# PIR-ESP-V10.net
KiCad netlist of a schematic drawn in EAGLE
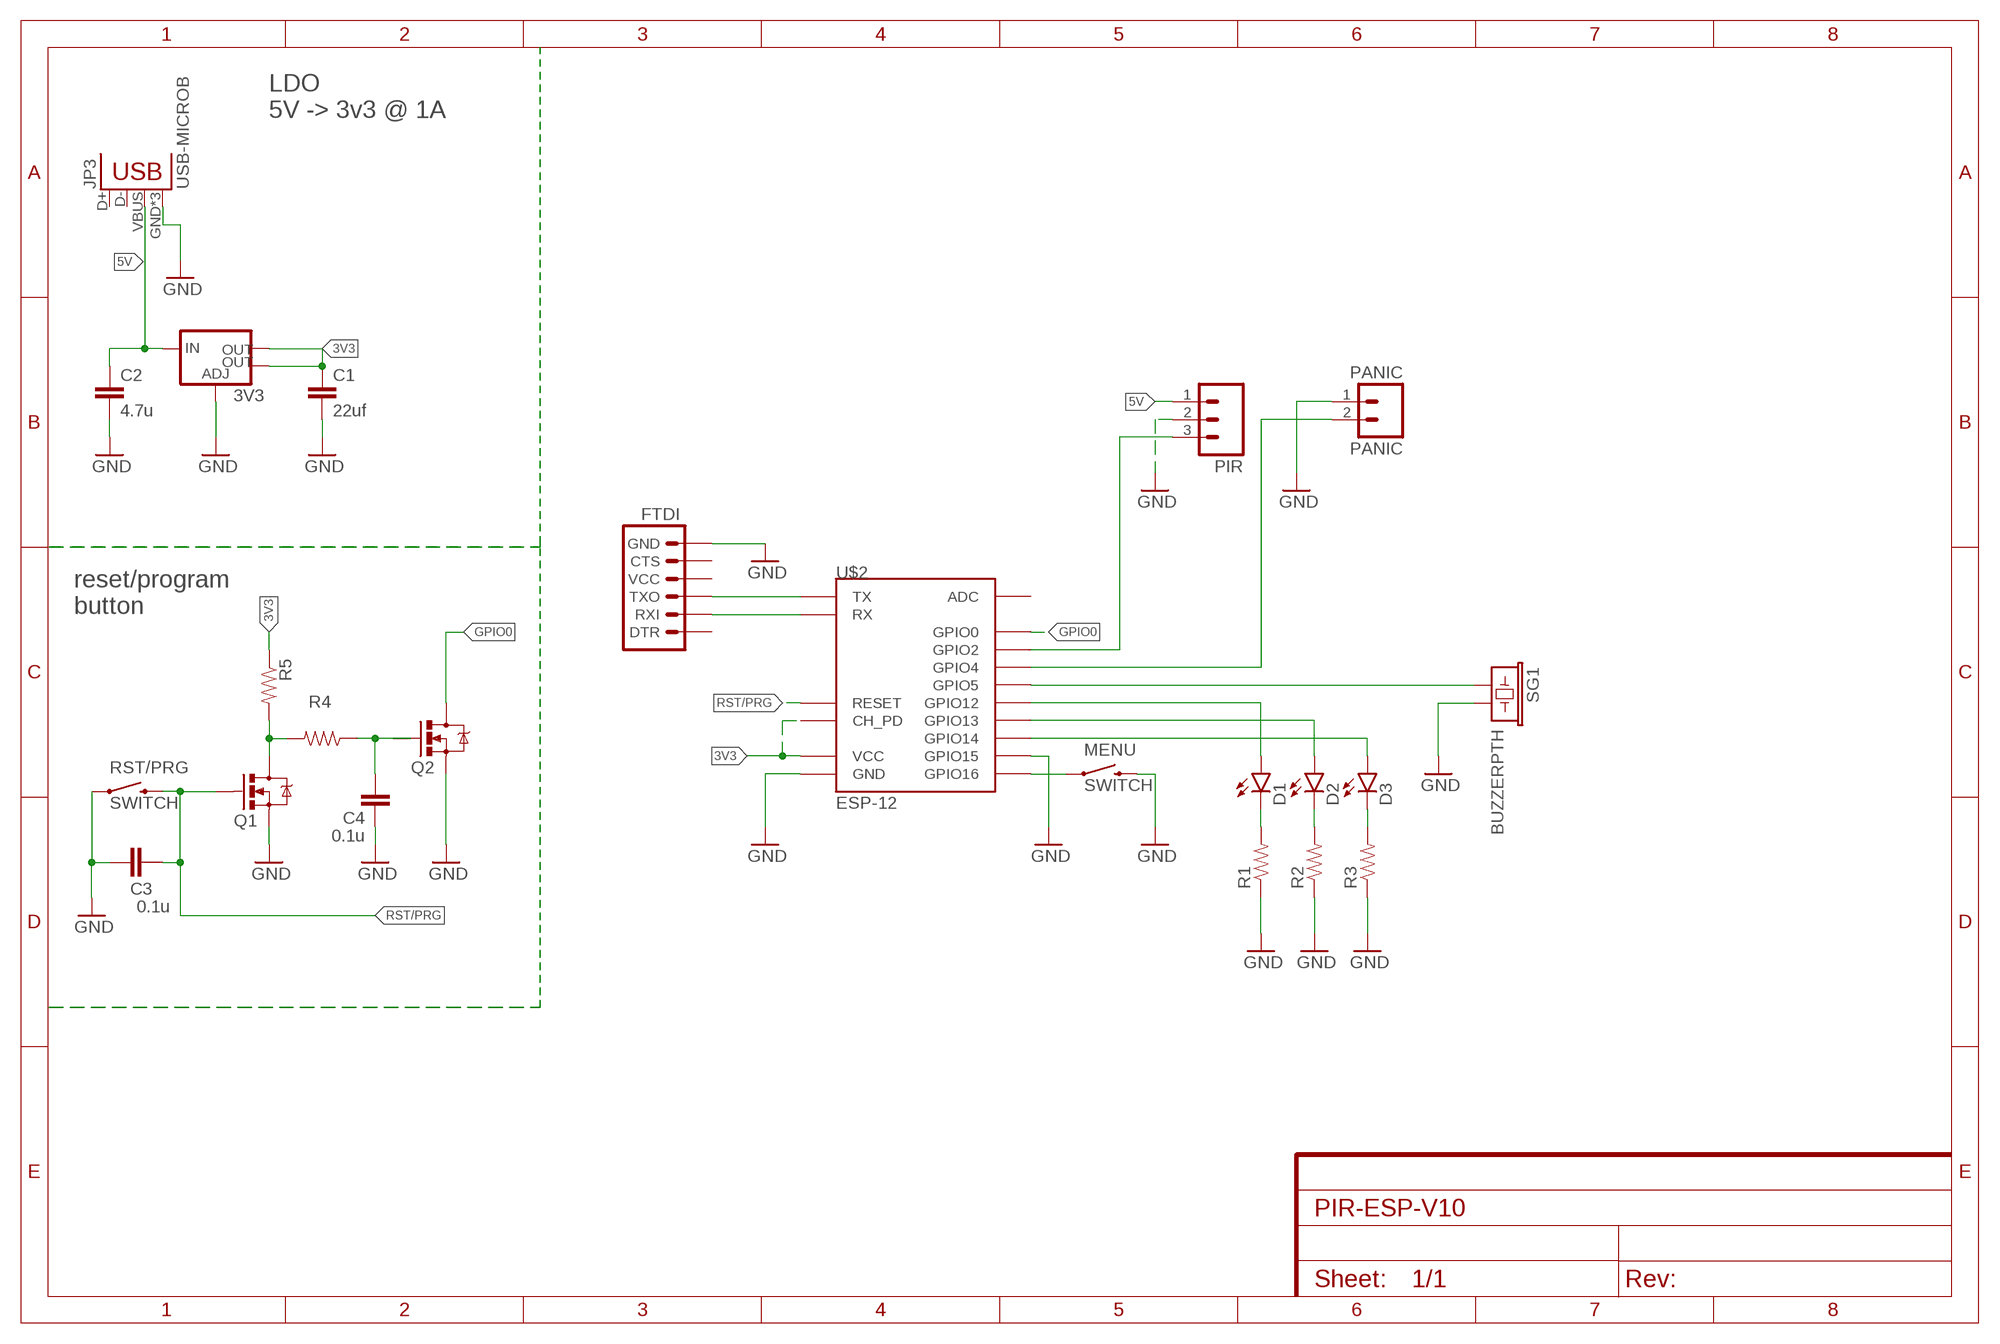
[diagram p0: schematic, sheet 1]

(export (version "E")
  (design (tool "Eeschema 10.0.6"))
  (components
    (comp (ref "3V3")
      (value "V_REG_LM1117SOT223")
      (footprint "eagle-import:SOT223")
      (libsource (lib "eagle-import") (part "V_REG_LM1117SOT223"))
    )
    (comp (ref "C1")
      (value "22uf")
      (footprint "eagle-import:1206")
      (libsource (lib "eagle-import") (part "CAP1206"))
    )
    (comp (ref "C2")
      (value "4.7u")
      (footprint "eagle-import:1206")
      (libsource (lib "eagle-import") (part "CAP1206"))
    )
    (comp (ref "C3")
      (value "0.1u")
      (footprint "eagle-import:1206")
      (libsource (lib "eagle-import") (part "CAP1206"))
    )
    (comp (ref "C4")
      (value "0.1u")
      (footprint "eagle-import:1206")
      (libsource (lib "eagle-import") (part "CAP1206"))
    )
    (comp (ref "D1")
      (value "LED5MM")
      (footprint "eagle-import:LED5MM")
      (libsource (lib "eagle-import") (part "LED5MM"))
    )
    (comp (ref "D2")
      (value "LED5MM")
      (footprint "eagle-import:LED5MM")
      (libsource (lib "eagle-import") (part "LED5MM"))
    )
    (comp (ref "D3")
      (value "LED5MM")
      (footprint "eagle-import:LED5MM")
      (libsource (lib "eagle-import") (part "LED5MM"))
    )
    (comp (ref "FTDI")
      (value "ARDUINO_SERIAL_PROGRAMLOCK")
      (footprint "eagle-import:1X06_LOCK")
      (libsource (lib "eagle-import") (part "ARDUINO_SERIAL_PROGRAMLOCK"))
    )
    (comp (ref "JP3")
      (value "USB-MICROB")
      (footprint "eagle-import:USB-MICROB")
      (libsource (lib "eagle-import") (part "USB-MICROB"))
    )
    (comp (ref "MENU")
      (value "SWITCH")
      (footprint "eagle-import:TACTILE-PTH-SIDEEZ")
      (libsource (lib "eagle-import") (part "SWITCH-MOMENTARY-2SIDE_EZ"))
    )
    (comp (ref "PANIC")
      (value "PANIC")
      (footprint "eagle-import:1X02_LONGPADS")
      (libsource (lib "eagle-import") (part "M02PTH3"))
    )
    (comp (ref "PIR")
      (value "M03LONGPADS")
      (footprint "eagle-import:1X03_LONGPADS")
      (libsource (lib "eagle-import") (part "M03LONGPADS"))
    )
    (comp (ref "Q1")
      (value "200mA/50V")
      (footprint "eagle-import:SOT23-3")
      (libsource (lib "eagle-import") (part "MOSFET-NCHANNELBSS138"))
    )
    (comp (ref "Q2")
      (value "200mA/50V")
      (footprint "eagle-import:SOT23-3")
      (libsource (lib "eagle-import") (part "MOSFET-NCHANNELBSS138"))
    )
    (comp (ref "R1")
      (value "RESISTOR1206")
      (footprint "eagle-import:1206")
      (libsource (lib "eagle-import") (part "RESISTOR1206"))
    )
    (comp (ref "R2")
      (value "RESISTOR1206")
      (footprint "eagle-import:1206")
      (libsource (lib "eagle-import") (part "RESISTOR1206"))
    )
    (comp (ref "R3")
      (value "RESISTOR1206")
      (footprint "eagle-import:1206")
      (libsource (lib "eagle-import") (part "RESISTOR1206"))
    )
    (comp (ref "R4")
      (value "RESISTOR1206")
      (footprint "eagle-import:1206")
      (libsource (lib "eagle-import") (part "RESISTOR1206"))
    )
    (comp (ref "R5")
      (value "RESISTOR1206")
      (footprint "eagle-import:1206")
      (libsource (lib "eagle-import") (part "RESISTOR1206"))
    )
    (comp (ref "RST/PRG")
      (value "SWITCH")
      (footprint "eagle-import:TACTILE-PTH-SIDEEZ")
      (libsource (lib "eagle-import") (part "SWITCH-MOMENTARY-2SIDE_EZ"))
    )
    (comp (ref "SG1")
      (value "BUZZERPTH")
      (footprint "eagle-import:BUZZER-12MM")
      (libsource (lib "eagle-import") (part "BUZZERPTH"))
    )
    (comp (ref "U$2")
      (value "ESP-12")
      (footprint "eagle-import:ESP-12")
      (libsource (lib "eagle-import") (part "ESP-12"))
    )
  )
  (nets
    (net (code "1") (name "3V3") (class "Default")
      (node (ref "3V3") (pin "2") (pinfunction "OUT_2") (pintype "output"))
      (node (ref "3V3") (pin "4") (pinfunction "OUT_4") (pintype "output"))
      (node (ref "C1") (pin "1") (pinfunction "1_1") (pintype "passive"))
      (node (ref "R5") (pin "1") (pinfunction "1_1") (pintype "passive"))
      (node (ref "U$2") (pin "CH_PD") (pinfunction "CH_PD_CH_PD") (pintype "bidirectional"))
      (node (ref "U$2") (pin "VCC") (pinfunction "VCC_VCC") (pintype "bidirectional"))
    )
    (net (code "2") (name "5V") (class "Default")
      (node (ref "3V3") (pin "3") (pinfunction "IN_3") (pintype "input"))
      (node (ref "C2") (pin "1") (pinfunction "1_1") (pintype "passive"))
      (node (ref "JP3") (pin "VBUS") (pinfunction "VBUS_VBUS") (pintype "bidirectional"))
      (node (ref "PIR") (pin "1") (pinfunction "1_1") (pintype "passive"))
    )
    (net (code "3") (name "GND") (class "Default")
      (node (ref "3V3") (pin "1") (pinfunction "ADJ_1") (pintype "input"))
      (node (ref "C1") (pin "2") (pinfunction "2_2") (pintype "passive"))
      (node (ref "C2") (pin "2") (pinfunction "2_2") (pintype "passive"))
      (node (ref "C3") (pin "1") (pinfunction "1_1") (pintype "passive"))
      (node (ref "C4") (pin "1") (pinfunction "1_1") (pintype "passive"))
      (node (ref "FTDI") (pin "6") (pinfunction "GND_6") (pintype "passive"))
      (node (ref "JP3") (pin "GND") (pinfunction "GND_GND") (pintype "bidirectional"))
      (node (ref "JP3") (pin "MT1") (pinfunction "GND_MT1") (pintype "bidirectional"))
      (node (ref "JP3") (pin "MT2") (pinfunction "GND_MT2") (pintype "bidirectional"))
      (node (ref "MENU") (pin "2") (pinfunction "2_2") (pintype "passive"))
      (node (ref "PANIC") (pin "1") (pinfunction "1_1") (pintype "passive"))
      (node (ref "PIR") (pin "2") (pinfunction "2_2") (pintype "passive"))
      (node (ref "Q1") (pin "2") (pinfunction "S_2") (pintype "passive"))
      (node (ref "Q2") (pin "2") (pinfunction "S_2") (pintype "passive"))
      (node (ref "R1") (pin "1") (pinfunction "1_1") (pintype "passive"))
      (node (ref "R2") (pin "1") (pinfunction "1_1") (pintype "passive"))
      (node (ref "R3") (pin "1") (pinfunction "1_1") (pintype "passive"))
      (node (ref "RST/PRG") (pin "1") (pinfunction "1_1") (pintype "passive"))
      (node (ref "SG1") (pin "-") (pinfunction "2_-") (pintype "passive"))
      (node (ref "U$2") (pin "GND") (pinfunction "GND_GND") (pintype "bidirectional"))
      (node (ref "U$2") (pin "GPIO15") (pinfunction "GPIO15_GPIO15") (pintype "bidirectional"))
    )
    (net (code "4") (name "GPIO0") (class "Default")
      (node (ref "Q2") (pin "3") (pinfunction "D_3") (pintype "passive"))
      (node (ref "U$2") (pin "GPIO0") (pinfunction "GPIO0_GPIO0") (pintype "bidirectional"))
    )
    (net (code "5") (name "Net-(D1-C)") (class "Default")
      (node (ref "D1") (pin "K") (pinfunction "C_K") (pintype "passive"))
      (node (ref "R1") (pin "2") (pinfunction "2_2") (pintype "passive"))
    )
    (net (code "6") (name "Net-(D1-PadA)") (class "Default")
      (node (ref "D1") (pin "A") (pinfunction "A_A") (pintype "passive"))
      (node (ref "U$2") (pin "GPIO12") (pinfunction "GPIO12_GPIO12") (pintype "bidirectional"))
    )
    (net (code "7") (name "Net-(D2-C)") (class "Default")
      (node (ref "D2") (pin "K") (pinfunction "C_K") (pintype "passive"))
      (node (ref "R2") (pin "2") (pinfunction "2_2") (pintype "passive"))
    )
    (net (code "8") (name "Net-(D2-PadA)") (class "Default")
      (node (ref "D2") (pin "A") (pinfunction "A_A") (pintype "passive"))
      (node (ref "U$2") (pin "GPIO13") (pinfunction "GPIO13_GPIO13") (pintype "bidirectional"))
    )
    (net (code "9") (name "Net-(D3-C)") (class "Default")
      (node (ref "D3") (pin "K") (pinfunction "C_K") (pintype "passive"))
      (node (ref "R3") (pin "2") (pinfunction "2_2") (pintype "passive"))
    )
    (net (code "10") (name "Net-(D3-PadA)") (class "Default")
      (node (ref "D3") (pin "A") (pinfunction "A_A") (pintype "passive"))
      (node (ref "U$2") (pin "GPIO14") (pinfunction "GPIO14_GPIO14") (pintype "bidirectional"))
    )
    (net (code "11") (name "Net-(FTDI-RXI)") (class "Default")
      (node (ref "FTDI") (pin "2") (pinfunction "RXI_2") (pintype "passive"))
      (node (ref "U$2") (pin "RX") (pinfunction "RX_RX") (pintype "bidirectional"))
    )
    (net (code "12") (name "Net-(FTDI-TXO)") (class "Default")
      (node (ref "FTDI") (pin "3") (pinfunction "TXO_3") (pintype "passive"))
      (node (ref "U$2") (pin "TX") (pinfunction "TX_TX") (pintype "bidirectional"))
    )
    (net (code "13") (name "Net-(MENU-Pad1)") (class "Default")
      (node (ref "MENU") (pin "1") (pinfunction "1_1") (pintype "passive"))
      (node (ref "U$2") (pin "GPIO16") (pinfunction "GPIO16_GPIO16") (pintype "bidirectional"))
    )
    (net (code "14") (name "Net-(PANIC-Pad2)") (class "Default")
      (node (ref "PANIC") (pin "2") (pinfunction "2_2") (pintype "passive"))
      (node (ref "U$2") (pin "GPIO4") (pinfunction "GPIO4_GPIO4") (pintype "bidirectional"))
    )
    (net (code "15") (name "Net-(PIR-Pad3)") (class "Default")
      (node (ref "PIR") (pin "3") (pinfunction "3_3") (pintype "passive"))
      (node (ref "U$2") (pin "GPIO2") (pinfunction "GPIO2_GPIO2") (pintype "bidirectional"))
    )
    (net (code "16") (name "Net-(Q1-D)") (class "Default")
      (node (ref "Q1") (pin "3") (pinfunction "D_3") (pintype "passive"))
      (node (ref "R4") (pin "2") (pinfunction "2_2") (pintype "passive"))
      (node (ref "R5") (pin "2") (pinfunction "2_2") (pintype "passive"))
    )
    (net (code "17") (name "Net-(Q2-G)") (class "Default")
      (node (ref "C4") (pin "2") (pinfunction "2_2") (pintype "passive"))
      (node (ref "Q2") (pin "1") (pinfunction "G_1") (pintype "passive"))
      (node (ref "R4") (pin "1") (pinfunction "1_1") (pintype "passive"))
    )
    (net (code "18") (name "Net-(SG1-1)") (class "Default")
      (node (ref "SG1") (pin "+") (pinfunction "1_+") (pintype "passive"))
      (node (ref "U$2") (pin "GPIO5") (pinfunction "GPIO5_GPIO5") (pintype "bidirectional"))
    )
    (net (code "19") (name "RST{slash}PRG") (class "Default")
      (node (ref "C3") (pin "2") (pinfunction "2_2") (pintype "passive"))
      (node (ref "Q1") (pin "1") (pinfunction "G_1") (pintype "passive"))
      (node (ref "RST/PRG") (pin "2") (pinfunction "2_2") (pintype "passive"))
      (node (ref "U$2") (pin "RESET") (pinfunction "RESET_RESET") (pintype "bidirectional"))
    )
    (net (code "20") (name "unconnected-(FTDI-CTS-Pad5)") (class "Default")
      (node (ref "FTDI") (pin "5") (pinfunction "CTS_5") (pintype "passive"))
    )
    (net (code "21") (name "unconnected-(FTDI-DTR-Pad1)") (class "Default")
      (node (ref "FTDI") (pin "1") (pinfunction "DTR_1") (pintype "passive"))
    )
    (net (code "22") (name "unconnected-(FTDI-VCC-Pad4)") (class "Default")
      (node (ref "FTDI") (pin "4") (pinfunction "VCC_4") (pintype "passive"))
    )
    (net (code "23") (name "unconnected-(JP3-PadD+)") (class "Default")
      (node (ref "JP3") (pin "D+") (pinfunction "D+_D+") (pintype "bidirectional"))
    )
    (net (code "24") (name "unconnected-(JP3-PadD-)") (class "Default")
      (node (ref "JP3") (pin "D-") (pinfunction "D-_D-") (pintype "bidirectional"))
    )
    (net (code "25") (name "unconnected-(U$2-PadADC)") (class "Default")
      (node (ref "U$2") (pin "ADC") (pinfunction "ADC_ADC") (pintype "bidirectional"))
    )
  )
)
